# Charging_1AOut2.net
KiCad netlist of a schematic drawn in Altium Designer
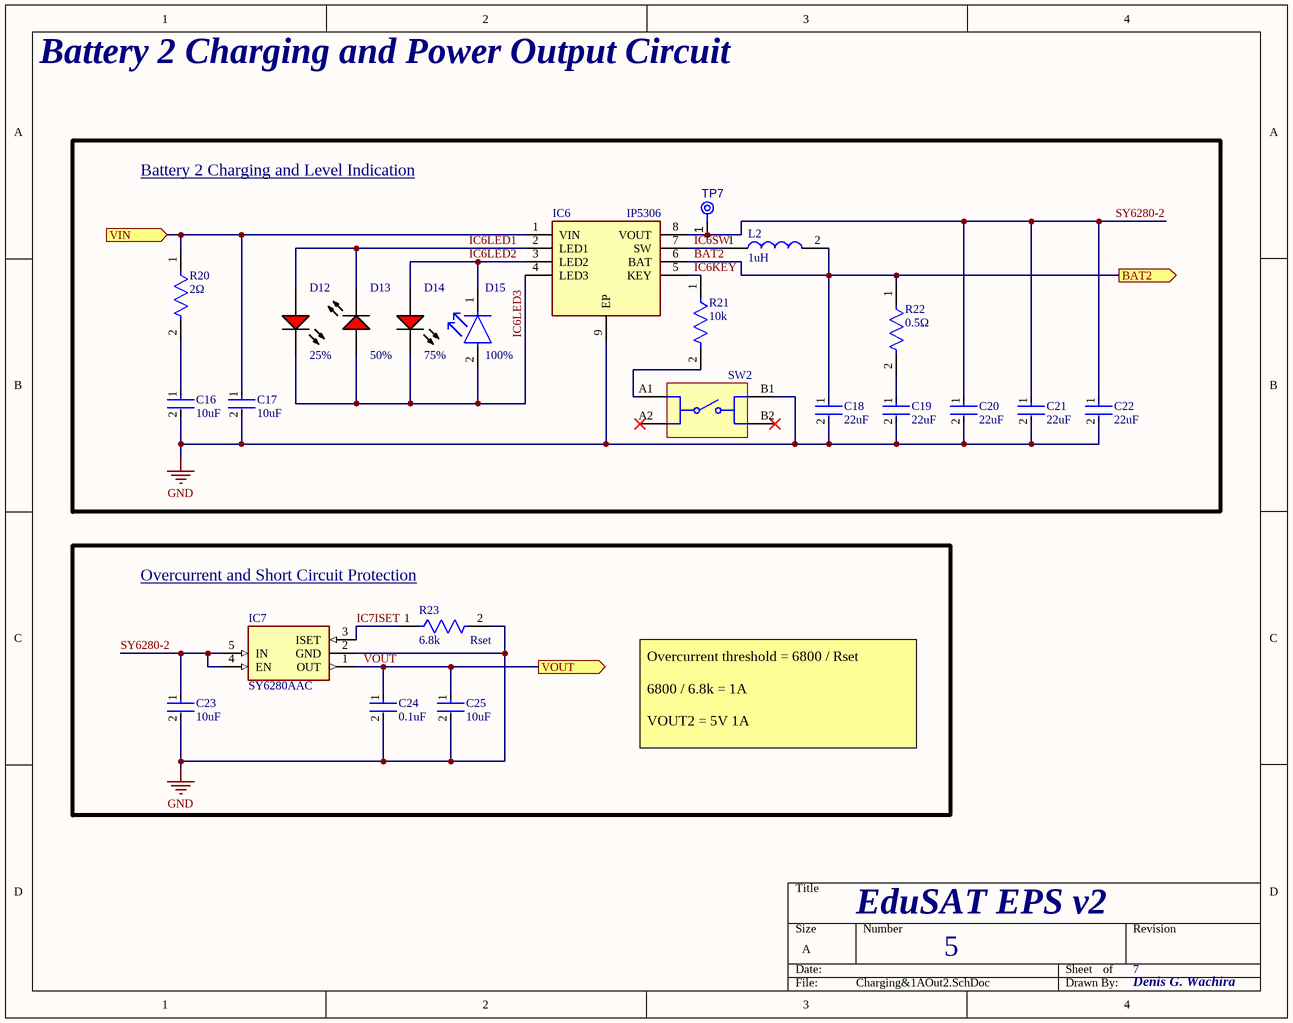
[diagram p0: Charging&1AOut2.SchDoc]

(export (version "E")
  (design (tool "Eeschema 10.0.6"))
  (components
    (comp (ref "C16")
      (value "10uF")
      (footprint "FP-CL21-IPC_A")
      (description "CL21 Series 0805 10uF 25V ±10% Tolerance X5R Multilayer Ceramic Chip Capacitor CL21A106KAYNNNE")
      (fields (field (name "TOLERANCE") "10%"))
      (libsource (lib "Altium Content Vault") (part "b4654b650e69147ec39a6b967a45e02"))
    )
    (comp (ref "C17")
      (value "10uF")
      (footprint "FP-CL21-IPC_A")
      (description "CL21 Series 0805 10uF 25V ±10% Tolerance X5R Multilayer Ceramic Chip Capacitor CL21A106KAYNNNE")
      (fields (field (name "TOLERANCE") "10%"))
      (libsource (lib "Altium Content Vault") (part "b4654b650e69147ec39a6b967a45e02"))
    )
    (comp (ref "C18")
      (value "22uF")
      (footprint "FP-CL21-IPC_C")
      (description "CL21 Series 0805 22uF 25V ±20% Tolerance X5R Multilayer Ceramic Chip Capacitor CL21A226MAYNNNE")
      (libsource (lib "Altium Content Vault") (part "b4654b650e69147ec39a6b967a45e02"))
    )
    (comp (ref "C19")
      (value "22uF")
      (footprint "FP-CL21-IPC_C")
      (description "CL21 Series 0805 22uF 25V ±20% Tolerance X5R Multilayer Ceramic Chip Capacitor CL21A226MAYNNNE")
      (libsource (lib "Altium Content Vault") (part "b4654b650e69147ec39a6b967a45e02"))
    )
    (comp (ref "C20")
      (value "22uF")
      (footprint "FP-CL21-IPC_C")
      (description "CL21 Series 0805 22uF 25V ±20% Tolerance X5R Multilayer Ceramic Chip Capacitor CL21A226MAYNNNE")
      (libsource (lib "Altium Content Vault") (part "b4654b650e69147ec39a6b967a45e02"))
    )
    (comp (ref "C21")
      (value "22uF")
      (footprint "FP-CL21-IPC_C")
      (description "CL21 Series 0805 22uF 25V ±20% Tolerance X5R Multilayer Ceramic Chip Capacitor CL21A226MAYNNNE")
      (libsource (lib "Altium Content Vault") (part "b4654b650e69147ec39a6b967a45e02"))
    )
    (comp (ref "C22")
      (value "22uF")
      (footprint "FP-CL21-IPC_C")
      (description "CL21 Series 0805 22uF 25V ±20% Tolerance X5R Multilayer Ceramic Chip Capacitor CL21A226MAYNNNE")
      (libsource (lib "Altium Content Vault") (part "b4654b650e69147ec39a6b967a45e02"))
    )
    (comp (ref "C23")
      (value "10uF")
      (footprint "FP-CL21-IPC_A")
      (description "CL21 Series 0805 10uF 25V ±10% Tolerance X5R Multilayer Ceramic Chip Capacitor CL21A106KAYNNNE")
      (fields (field (name "TOLERANCE") "10%"))
      (libsource (lib "Altium Content Vault") (part "b4654b650e69147ec39a6b967a45e02"))
    )
    (comp (ref "C24")
      (value "0.1uF")
      (footprint "FP-CL21-IPC_A")
      (description "50V 0.1uF X7R ±10% 0805 Multilayer Ceramic Capacitors MLCC - SMD/SMT ROHS TCC0805X7R104K500DT")
      (fields (field (name "TOLERANCE") "10%"))
      (libsource (lib "Altium Content Vault") (part "b4654b650e69147ec39a6b967a45e02"))
    )
    (comp (ref "C25")
      (value "10uF")
      (footprint "FP-CL21-IPC_A")
      (description "CL21 Series 0805 10uF 25V ±10% Tolerance X5R Multilayer Ceramic Chip Capacitor CL21A106KAYNNNE")
      (fields (field (name "TOLERANCE") "10%"))
      (libsource (lib "Altium Content Vault") (part "b4654b650e69147ec39a6b967a45e02"))
    )
    (comp (ref "D12")
      (value "25%")
      (footprint "LTST-C170KRKT_V")
      (description "LED Red,KT-0805R")
      (fields (field (name "MANUFACTURER") "Lite-On"))
      (libsource (lib "Altium Content Vault") (part "LED-RED-AK-2"))
    )
    (comp (ref "D13")
      (value "50%")
      (footprint "LTST-C170KRKT_V")
      (description "LED Red, KT-0805R")
      (fields (field (name "MANUFACTURER") "Lite-On"))
      (libsource (lib "Altium Content Vault") (part "LED-RED-AK-2"))
    )
    (comp (ref "D14")
      (value "75%")
      (footprint "LTST-C170KRKT_V")
      (description "LED Red, KT-0805R")
      (fields (field (name "MANUFACTURER") "Lite-On"))
      (libsource (lib "Altium Content Vault") (part "LED-RED-AK-2"))
    )
    (comp (ref "D15")
      (value "100%")
      (footprint "FP-LTST-C170GKT-MFG")
      (description "LED GREEN CLEAR SMD KT-0805G")
      (fields (field (name "VOLTAGE") "5V"))
      (libsource (lib "Altium Content Vault") (part "8706943c75ba83719d021d2fdc84c58"))
    )
    (comp (ref "IC6")
      (value "IP5306")
      (footprint "SamacSys:SOIC127P600X165-9N")
      (description "Integrated Circuit")
      (libsource (lib "IP5306") (part "IP5306"))
    )
    (comp (ref "IC7")
      (value "SY6280AAC")
      (footprint "SamacSys:SOT95P285X140-5N")
      (description "Integrated Circuit")
      (libsource (lib "*") (part "SY6280AAC"))
    )
    (comp (ref "L2")
      (value "1uH")
      (footprint "SamacSys:INDPM7366X300N")
      (description "Inductor MCS0630-1R0MN2")
      (fields (field (name "MANUFACTURER_PART_NUMBER") "MCS0630-1R0MN2"))
      (libsource (lib "*") (part "MCS0630-2R2MN2"))
    )
    (comp (ref "R20")
      (value "2Ω")
      (footprint "FP-CR0805-IPC_B")
      (description "Thick Film Chip Resistors 0805 2Ω 0.125W 1% 250ppm/°C \r\nRS-05L2R00FT")
      (fields (field (name "TOLERANCE") "1%"))
      (libsource (lib "Altium Content Vault") (part "1029c3af85768c4190bb7ad29bc67b5"))
    )
    (comp (ref "R21")
      (value "10k")
      (footprint "FP-MCR10-IPC_C")
      (description "Thick Film Chip Resistor, 0805, 10kΩ, 1%, 100ppm/°C, 0.125W, 150V \r\n0805W8F1002T5E")
      (fields (field (name "TOLERANCE") "1%"))
      (libsource (lib "Altium Content Vault") (part "1029c3af85768c4190bb7ad29bc67b5"))
    )
    (comp (ref "R22")
      (value "0.5Ω")
      (footprint "FP-MCR10-IPC_C")
      (description "Thick Film Chip Resistor, 0805, 0.5R, 1%, 100ppm/°C, 0.125W, 150V \r\n0805W8F500LT5E")
      (fields (field (name "TOLERANCE") "1%"))
      (libsource (lib "Altium Content Vault") (part "1029c3af85768c4190bb7ad29bc67b5"))
    )
    (comp (ref "R23")
      (value "6.8k          Rset")
      (footprint "FP-MCR10-IPC_C")
      (description "Thick Film Chip Resistor, 0805, 6.8kΩ, 1%, 100ppm/°C, 0.125W, 150V \r\n0805W8F6801T5E")
      (fields (field (name "TOLERANCE") "1%"))
      (libsource (lib "Altium Content Vault") (part "1029c3af85768c4190bb7ad29bc67b5"))
    )
    (comp (ref "SW2")
      (value "430181038816")
      (footprint "WS-TASV_L4.5W4.5H3.8_430181038816")
      (libsource (lib "Altium Content Vault") (part "SPST-NO_4P"))
    )
    (comp (ref "TP7")
      (value "TPAD6R")
      (footprint "TP06R")
      (description "0.6mm round")
      (libsource (lib "University of Nairobi") (part "CMP-001-0001-4"))
    )
  )
  (nets
    (net (code "1") (name "/BAT2") (class "Default")
      (node (ref "C18") (pin "1") (pinfunction "1_1") (pintype "passive"))
      (node (ref "IC6") (pin "6") (pinfunction "BAT_6") (pintype "passive"))
      (node (ref "L2") (pin "2") (pinfunction "2_2") (pintype "passive"))
      (node (ref "R22") (pin "1") (pinfunction "1_1") (pintype "passive"))
    )
    (net (code "2") (name "/IC6KEY") (class "Default")
      (node (ref "IC6") (pin "5") (pinfunction "KEY_5") (pintype "passive"))
      (node (ref "R21") (pin "1") (pinfunction "1_1") (pintype "passive"))
    )
    (net (code "3") (name "/IC6LED1") (class "Default")
      (node (ref "D12") (pin "1") (pinfunction "A_1") (pintype "passive"))
      (node (ref "D13") (pin "2") (pinfunction "K_2") (pintype "passive"))
      (node (ref "IC6") (pin "2") (pinfunction "LED1_2") (pintype "passive"))
    )
    (net (code "4") (name "/IC6LED2") (class "Default")
      (node (ref "D14") (pin "1") (pinfunction "A_1") (pintype "passive"))
      (node (ref "D15") (pin "1") (pinfunction "C_1") (pintype "passive"))
      (node (ref "IC6") (pin "3") (pinfunction "LED2_3") (pintype "passive"))
    )
    (net (code "5") (name "/IC6LED3") (class "Default")
      (node (ref "D12") (pin "2") (pinfunction "K_2") (pintype "passive"))
      (node (ref "D13") (pin "1") (pinfunction "A_1") (pintype "passive"))
      (node (ref "D14") (pin "2") (pinfunction "K_2") (pintype "passive"))
      (node (ref "D15") (pin "2") (pinfunction "A_2") (pintype "passive"))
      (node (ref "IC6") (pin "4") (pinfunction "LED3_4") (pintype "passive"))
    )
    (net (code "6") (name "/IC6SW") (class "Default")
      (node (ref "IC6") (pin "7") (pinfunction "SW_7") (pintype "passive"))
      (node (ref "L2") (pin "1") (pinfunction "1_1") (pintype "passive"))
    )
    (net (code "7") (name "/IC7ISET") (class "Default")
      (node (ref "IC7") (pin "3") (pinfunction "ISET_3") (pintype "input"))
      (node (ref "R23") (pin "1") (pinfunction "1_1") (pintype "passive"))
    )
    (net (code "8") (name "/SY6280-2") (class "Default")
      (node (ref "C20") (pin "1") (pinfunction "1_1") (pintype "passive"))
      (node (ref "C21") (pin "1") (pinfunction "1_1") (pintype "passive"))
      (node (ref "C22") (pin "1") (pinfunction "1_1") (pintype "passive"))
      (node (ref "C23") (pin "1") (pinfunction "1_1") (pintype "passive"))
      (node (ref "IC6") (pin "8") (pinfunction "VOUT_8") (pintype "passive"))
      (node (ref "IC7") (pin "4") (pinfunction "EN_4") (pintype "input"))
      (node (ref "IC7") (pin "5") (pinfunction "IN_5") (pintype "input"))
      (node (ref "TP7") (pin "1") (pinfunction "TP_1") (pintype "passive"))
    )
    (net (code "9") (name "/VIN") (class "Default")
      (node (ref "C17") (pin "1") (pinfunction "1_1") (pintype "passive"))
      (node (ref "IC6") (pin "1") (pinfunction "VIN_1") (pintype "passive"))
      (node (ref "R20") (pin "1") (pinfunction "1_1") (pintype "passive"))
    )
    (net (code "10") (name "/VOUT") (class "Default")
      (node (ref "C24") (pin "1") (pinfunction "1_1") (pintype "passive"))
      (node (ref "C25") (pin "1") (pinfunction "1_1") (pintype "passive"))
      (node (ref "IC7") (pin "1") (pinfunction "OUT_1") (pintype "output"))
    )
    (net (code "11") (name "GND") (class "Default")
      (node (ref "C16") (pin "2") (pinfunction "2_2") (pintype "passive"))
      (node (ref "C17") (pin "2") (pinfunction "2_2") (pintype "passive"))
      (node (ref "C18") (pin "2") (pinfunction "2_2") (pintype "passive"))
      (node (ref "C19") (pin "2") (pinfunction "2_2") (pintype "passive"))
      (node (ref "C20") (pin "2") (pinfunction "2_2") (pintype "passive"))
      (node (ref "C21") (pin "2") (pinfunction "2_2") (pintype "passive"))
      (node (ref "C22") (pin "2") (pinfunction "2_2") (pintype "passive"))
      (node (ref "C23") (pin "2") (pinfunction "2_2") (pintype "passive"))
      (node (ref "C24") (pin "2") (pinfunction "2_2") (pintype "passive"))
      (node (ref "C25") (pin "2") (pinfunction "2_2") (pintype "passive"))
      (node (ref "IC6") (pin "9") (pinfunction "EP_9") (pintype "passive"))
      (node (ref "IC7") (pin "2") (pinfunction "GND_2") (pintype "power_in"))
      (node (ref "R23") (pin "2") (pinfunction "2_2") (pintype "passive"))
      (node (ref "SW2") (pin "B1") (pinfunction "B1_B1") (pintype "passive"))
    )
    (net (code "12") (name "Net-(C16-Pad1)") (class "Default")
      (node (ref "C16") (pin "1") (pinfunction "1_1") (pintype "passive"))
      (node (ref "R20") (pin "2") (pinfunction "2_2") (pintype "passive"))
    )
    (net (code "13") (name "Net-(C19-Pad1)") (class "Default")
      (node (ref "C19") (pin "1") (pinfunction "1_1") (pintype "passive"))
      (node (ref "R22") (pin "2") (pinfunction "2_2") (pintype "passive"))
    )
    (net (code "14") (name "Net-(R21-Pad2)") (class "Default")
      (node (ref "R21") (pin "2") (pinfunction "2_2") (pintype "passive"))
      (node (ref "SW2") (pin "A1") (pinfunction "A1_A1") (pintype "passive"))
    )
    (net (code "15") (name "unconnected-(SW2-PadA2)") (class "Default")
      (node (ref "SW2") (pin "A2") (pinfunction "A2_A2") (pintype "passive+no_connect"))
    )
    (net (code "16") (name "unconnected-(SW2-PadB2)") (class "Default")
      (node (ref "SW2") (pin "B2") (pinfunction "B2_B2") (pintype "passive+no_connect"))
    )
  )
)
